# ESP32_with_USBC.net
KiCad netlist of a schematic drawn in Altium Designer
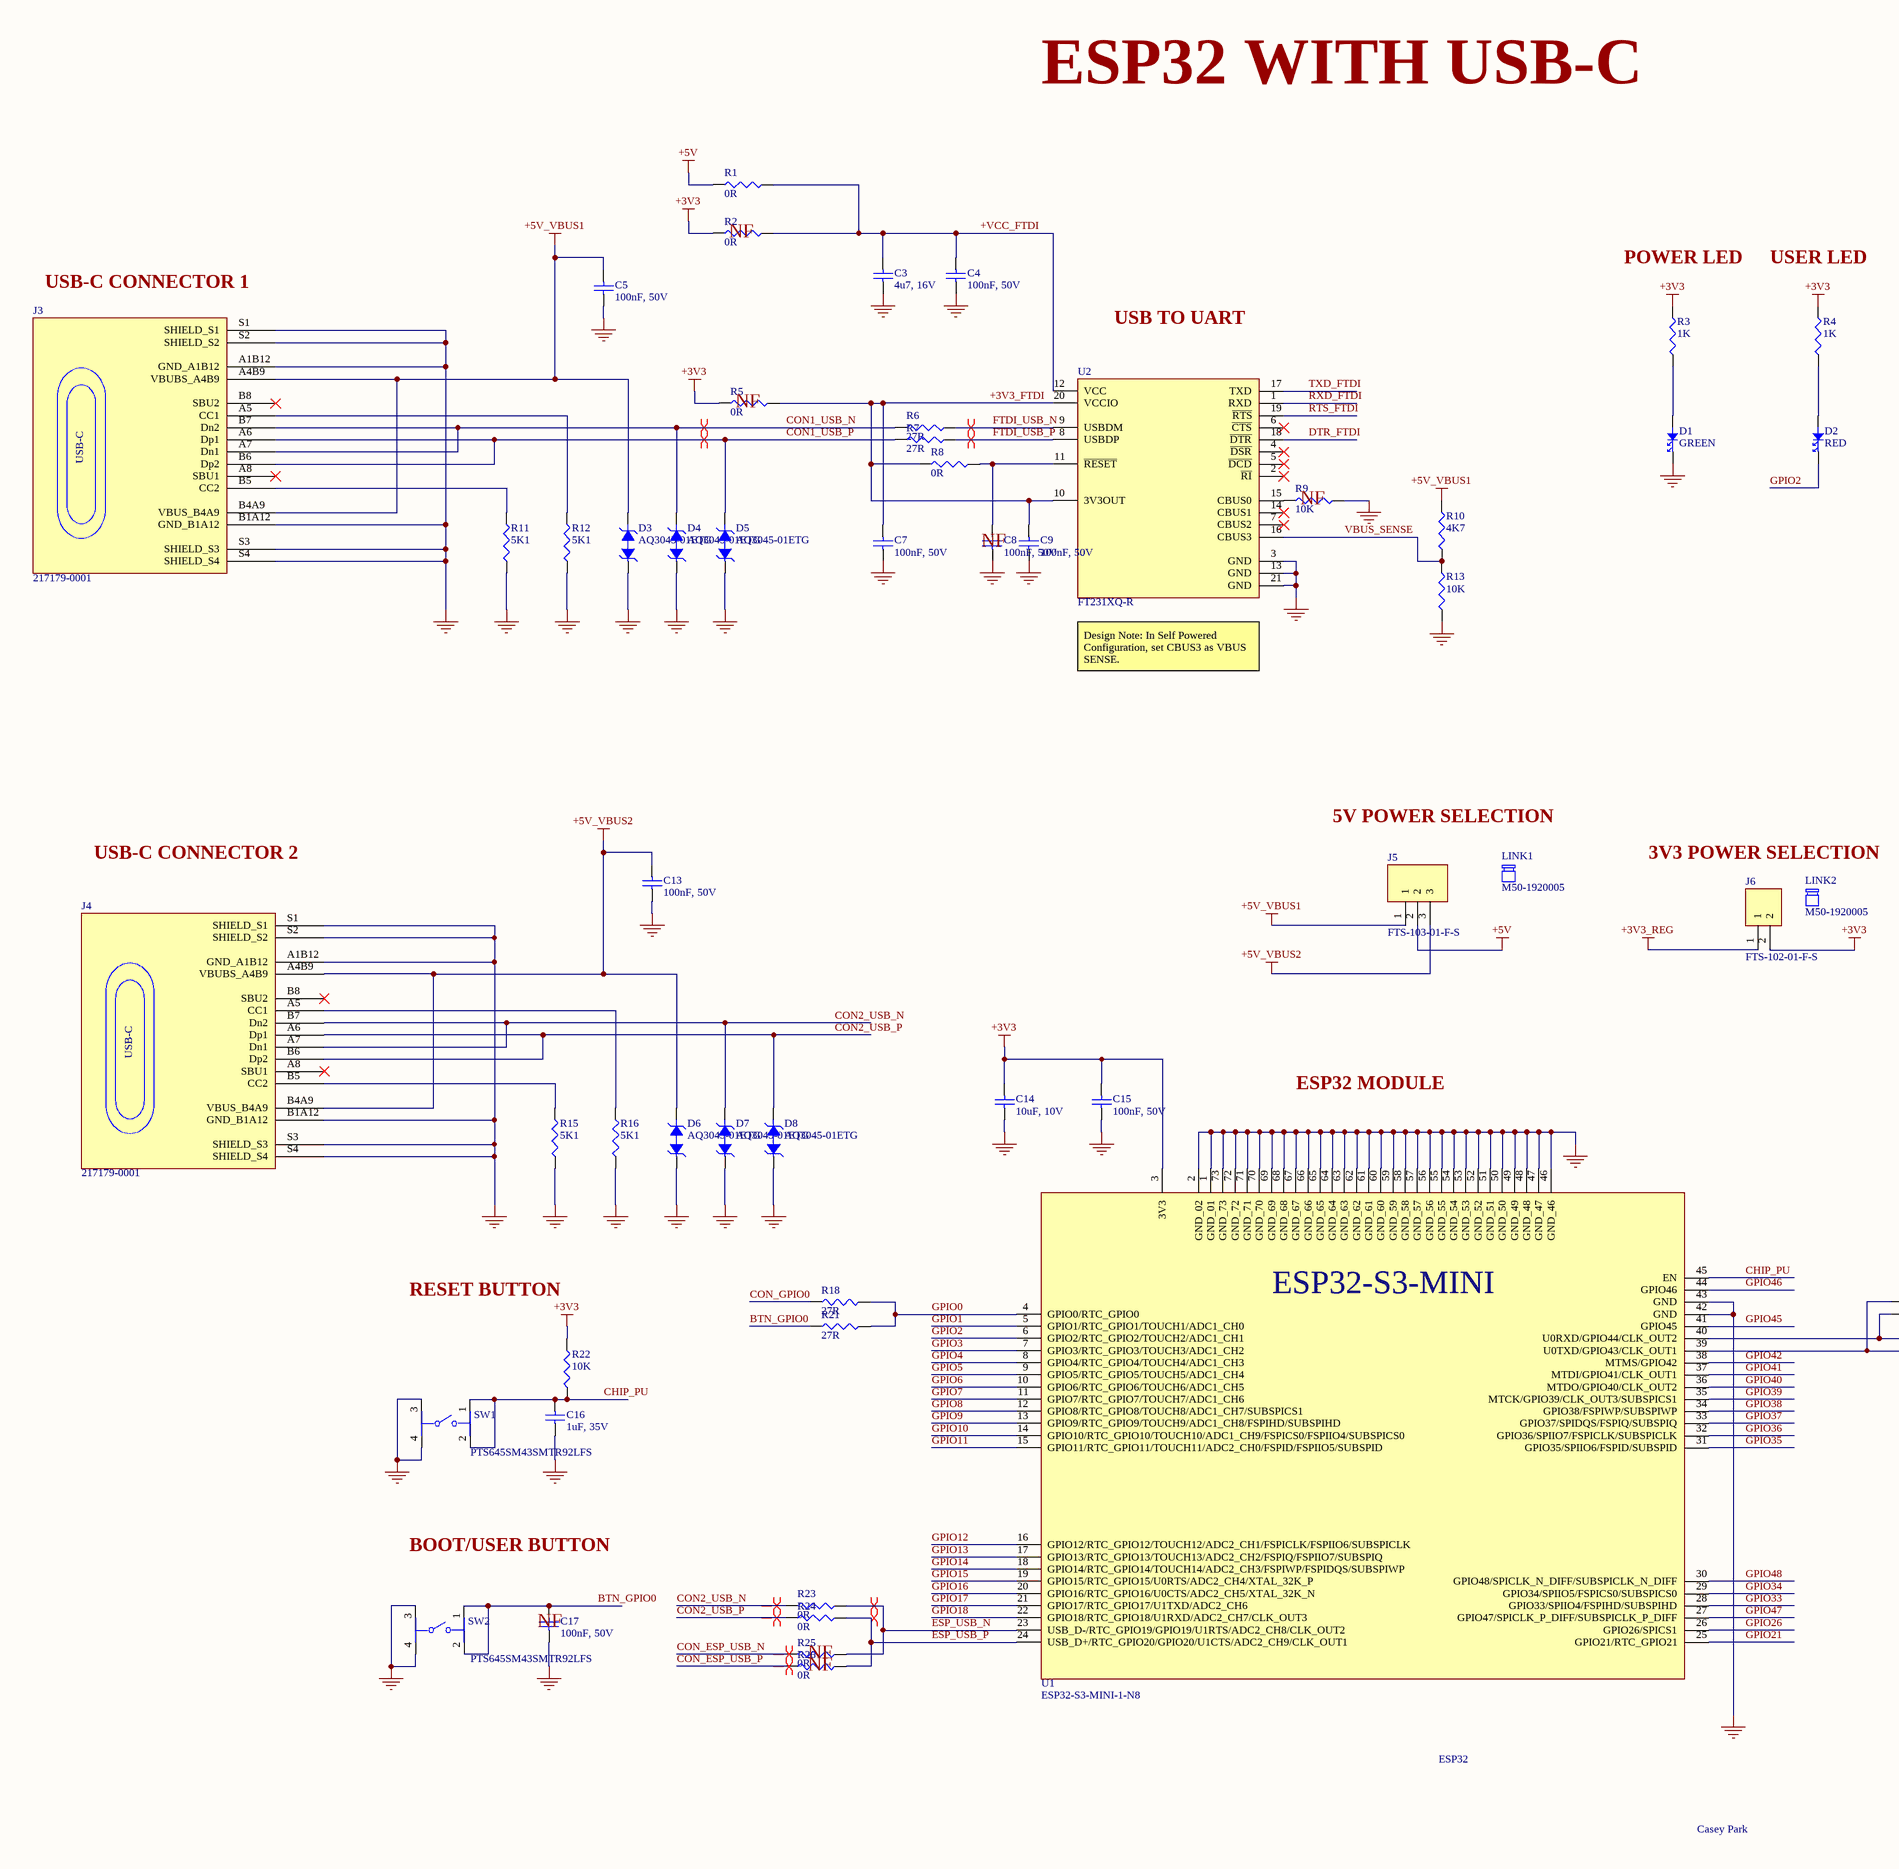
[diagram p0: ESP32 with USBC.SchDoc, left]
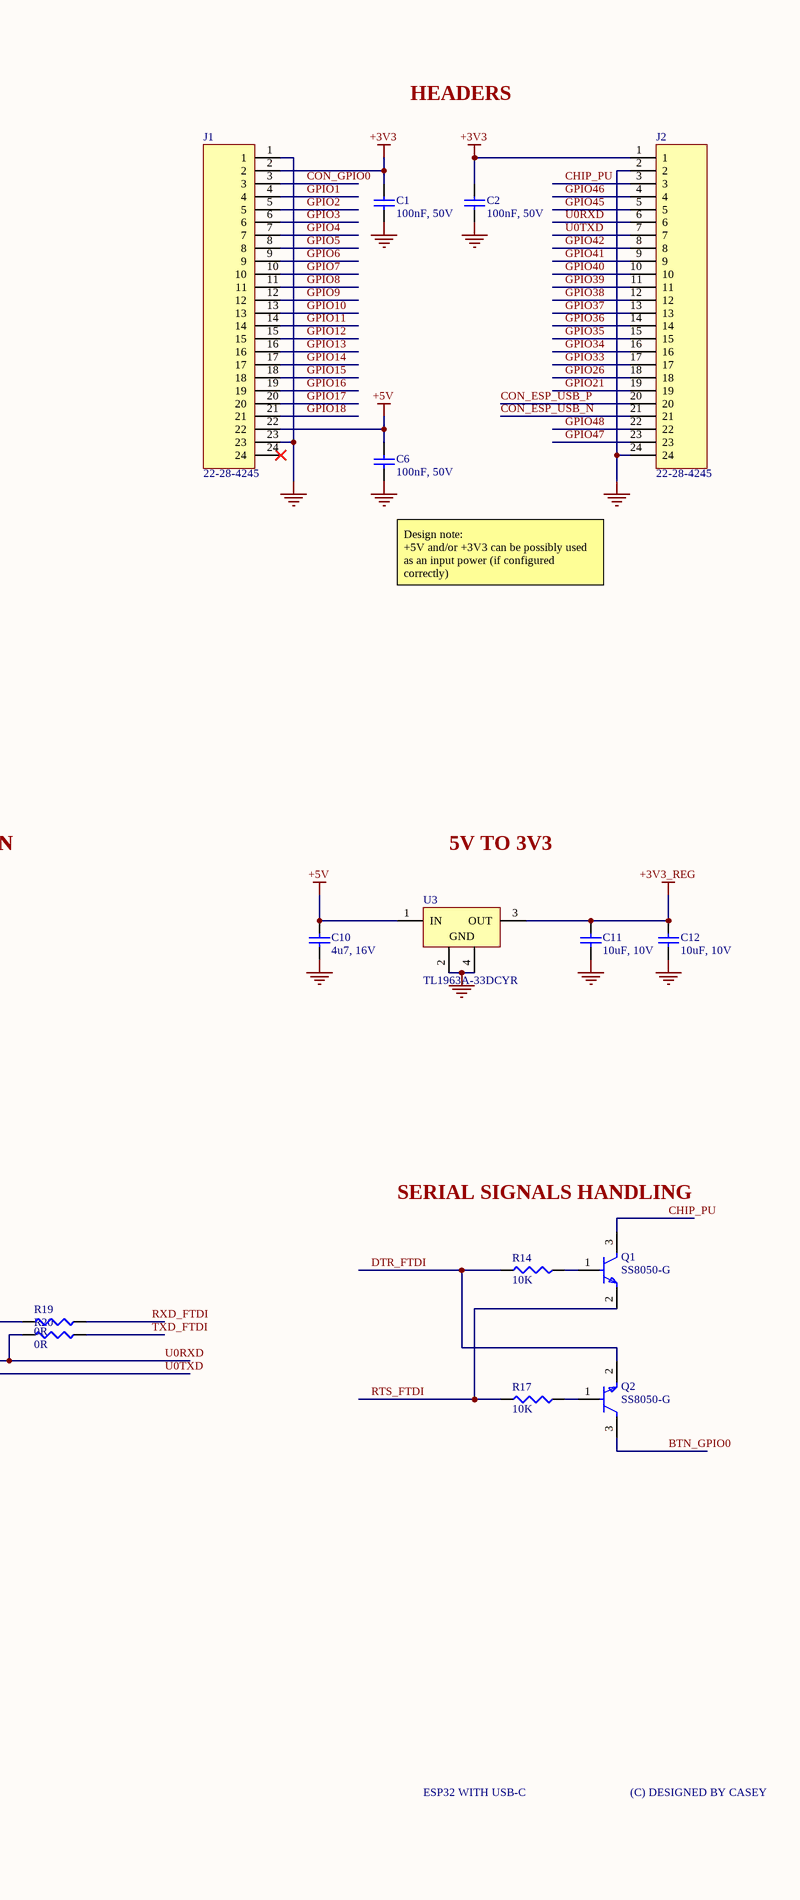
[diagram p1: ESP32 with USBC.SchDoc, right]

(export (version "E")
  (design (tool "Eeschema 10.0.6"))
  (components
    (comp (ref "C1")
      (value "100nF, 50V")
      (footprint "CAPC1005X70N")
      (description "CAP CER 0.1UF 50V X7R 0402")
      (fields
        (field (name "MANUFACTURER") "Samsung")
        (field (name "MANUFACTURER PART NUMBER") "CL05B104KB54PNC")
      )
      (libsource (lib "Schlib") (part "CL05B104KB54PNC"))
    )
    (comp (ref "C2")
      (value "100nF, 50V")
      (footprint "CAPC1005X70N")
      (description "CAP CER 0.1UF 50V X7R 0402")
      (fields
        (field (name "MANUFACTURER") "Samsung")
        (field (name "MANUFACTURER PART NUMBER") "CL05B104KB54PNC")
      )
      (libsource (lib "Schlib") (part "CL05B104KB54PNC"))
    )
    (comp (ref "C3")
      (value "4u7, 16V")
      (footprint "CAPC1005X70N")
      (description "CAP CER 4.7UF 16V X5R 0402")
      (fields
        (field (name "MANUFACTURER") "Samsung")
        (field (name "MANUFACTURER PART NUMBER") "CL05A475MO5NUNC")
      )
      (libsource (lib "Schlib") (part "CL05A475MO5NUNC"))
    )
    (comp (ref "C4")
      (value "100nF, 50V")
      (footprint "CAPC1005X70N")
      (description "CAP CER 0.1UF 50V X7R 0402")
      (fields
        (field (name "MANUFACTURER") "Samsung")
        (field (name "MANUFACTURER PART NUMBER") "CL05B104KB54PNC")
      )
      (libsource (lib "Schlib") (part "CL05B104KB54PNC"))
    )
    (comp (ref "C5")
      (value "100nF, 50V")
      (footprint "CAPC1005X70N")
      (description "CAP CER 0.1UF 50V X7R 0402")
      (fields
        (field (name "MANUFACTURER") "Samsung")
        (field (name "MANUFACTURER PART NUMBER") "CL05B104KB54PNC")
      )
      (libsource (lib "Schlib") (part "CL05B104KB54PNC"))
    )
    (comp (ref "C6")
      (value "100nF, 50V")
      (footprint "CAPC1005X70N")
      (description "CAP CER 0.1UF 50V X7R 0402")
      (fields
        (field (name "MANUFACTURER") "Samsung")
        (field (name "MANUFACTURER PART NUMBER") "CL05B104KB54PNC")
      )
      (libsource (lib "Schlib") (part "CL05B104KB54PNC"))
    )
    (comp (ref "C7")
      (value "100nF, 50V")
      (footprint "CAPC1005X70N")
      (description "CAP CER 0.1UF 50V X7R 0402")
      (fields
        (field (name "MANUFACTURER") "Samsung")
        (field (name "MANUFACTURER PART NUMBER") "CL05B104KB54PNC")
      )
      (libsource (lib "Schlib") (part "CL05B104KB54PNC"))
    )
    (comp (ref "C8")
      (value "100nF, 50V")
      (footprint "CAPC1005X70N")
      (description "CAP CER 0.1UF 50V X7R 0402")
      (fields
        (field (name "MANUFACTURER") "Samsung")
        (field (name "MANUFACTURER PART NUMBER") "CL05B104KB54PNC")
      )
      (libsource (lib "Schlib") (part "CL05B104KB54PNC"))
    )
    (comp (ref "C9")
      (value "100nF, 50V")
      (footprint "CAPC1005X70N")
      (description "CAP CER 0.1UF 50V X7R 0402")
      (fields
        (field (name "MANUFACTURER") "Samsung")
        (field (name "MANUFACTURER PART NUMBER") "CL05B104KB54PNC")
      )
      (libsource (lib "Schlib") (part "CL05B104KB54PNC"))
    )
    (comp (ref "C10")
      (value "4u7, 16V")
      (footprint "CAPC1005X70N")
      (description "CAP CER 4.7UF 16V X5R 0402")
      (fields
        (field (name "MANUFACTURER") "Samsung")
        (field (name "MANUFACTURER PART NUMBER") "CL05A475MO5NUNC")
      )
      (libsource (lib "Schlib") (part "CL05A475MO5NUNC"))
    )
    (comp (ref "C11")
      (value "10uF, 10V")
      (footprint "CAPC1005X70N")
      (description "10 µF ±20% 10V Ceramic Capacitor X5R 0402 (1005 Metric)")
      (fields
        (field (name "MANUFACTURER") "Samsung")
        (field (name "MANUFACTURER PART NUMBER") "CL05A106MP5NRNC")
      )
      (libsource (lib "Schlib") (part "CL05A106MP5NRNC"))
    )
    (comp (ref "C12")
      (value "10uF, 10V")
      (footprint "CAPC1005X70N")
      (description "10 µF ±20% 10V Ceramic Capacitor X5R 0402 (1005 Metric)")
      (fields
        (field (name "MANUFACTURER") "Samsung")
        (field (name "MANUFACTURER PART NUMBER") "CL05A106MP5NRNC")
      )
      (libsource (lib "Schlib") (part "CL05A106MP5NRNC"))
    )
    (comp (ref "C13")
      (value "100nF, 50V")
      (footprint "CAPC1005X70N")
      (description "CAP CER 0.1UF 50V X7R 0402")
      (fields
        (field (name "MANUFACTURER") "Samsung")
        (field (name "MANUFACTURER PART NUMBER") "CL05B104KB54PNC")
      )
      (libsource (lib "Schlib") (part "CL05B104KB54PNC"))
    )
    (comp (ref "C14")
      (value "10uF, 10V")
      (footprint "CAPC1005X70N")
      (description "10 µF ±20% 10V Ceramic Capacitor X5R 0402 (1005 Metric)")
      (fields
        (field (name "MANUFACTURER") "Samsung")
        (field (name "MANUFACTURER PART NUMBER") "CL05A106MP5NRNC")
      )
      (libsource (lib "Schlib") (part "CL05A106MP5NRNC"))
    )
    (comp (ref "C15")
      (value "100nF, 50V")
      (footprint "CAPC1005X70N")
      (description "CAP CER 0.1UF 50V X7R 0402")
      (fields
        (field (name "MANUFACTURER") "Samsung")
        (field (name "MANUFACTURER PART NUMBER") "CL05B104KB54PNC")
      )
      (libsource (lib "Schlib") (part "CL05B104KB54PNC"))
    )
    (comp (ref "C16")
      (value "1uF, 35V")
      (footprint "CAPC1005X70N")
      (description "CAP CER 1UF 35V X5R 0402")
      (fields
        (field (name "MANUFACTURER") "Samsung")
        (field (name "MANUFACTURER PART NUMBER") "CL05A105KL5NRNC")
      )
      (libsource (lib "Schlib") (part "CL05A105KL5NRNC"))
    )
    (comp (ref "C17")
      (value "100nF, 50V")
      (footprint "CAPC1005X70N")
      (description "CAP CER 0.1UF 50V X7R 0402")
      (fields
        (field (name "MANUFACTURER") "Samsung")
        (field (name "MANUFACTURER PART NUMBER") "CL05B104KB54PNC")
      )
      (libsource (lib "Schlib") (part "CL05B104KB54PNC"))
    )
    (comp (ref "D1")
      (value "GREEN")
      (footprint "LED0402GREEN")
      (description "LED YLW-GRN 0402 SMD")
      (fields
        (field (name "MANUFACTURER") "Vishay")
        (field (name "MANUFACTURER PART NUMBER") "VLMG1500-GS08")
      )
      (libsource (lib "Schlib") (part "VLMG1500-GS08"))
    )
    (comp (ref "D2")
      (value "RED")
      (footprint "LED0402RED")
      (description "LED RED 0402 SMD")
      (fields
        (field (name "MANUFACTURER") "Vishay")
        (field (name "MANUFACTURER PART NUMBER") "VLMS1500-GS08")
      )
      (libsource (lib "Schlib") (part "VLMS1500-GS08"))
    )
    (comp (ref "D3")
      (value "AQ3045-01ETG")
      (footprint "SOD882")
      (description "TVS DIODE 5.3VWM 12VC SOD882")
      (fields (field (name "MANUFACTURER") "Littelfuse") (field (name "LCSC PART NUMBER") "C3710326"))
      (libsource (lib "Schlib") (part "AQ3045-01ETG"))
    )
    (comp (ref "D4")
      (value "AQ3045-01ETG")
      (footprint "SOD882")
      (description "TVS DIODE 5.3VWM 12VC SOD882")
      (fields (field (name "MANUFACTURER") "Littelfuse") (field (name "LCSC PART NUMBER") "C3710326"))
      (libsource (lib "Schlib") (part "AQ3045-01ETG"))
    )
    (comp (ref "D5")
      (value "AQ3045-01ETG")
      (footprint "SOD882")
      (description "TVS DIODE 5.3VWM 12VC SOD882")
      (fields (field (name "MANUFACTURER") "Littelfuse") (field (name "LCSC PART NUMBER") "C3710326"))
      (libsource (lib "Schlib") (part "AQ3045-01ETG"))
    )
    (comp (ref "D6")
      (value "AQ3045-01ETG")
      (footprint "SOD882")
      (description "TVS DIODE 5.3VWM 12VC SOD882")
      (fields (field (name "MANUFACTURER") "Littelfuse") (field (name "LCSC PART NUMBER") "C3710326"))
      (libsource (lib "Schlib") (part "AQ3045-01ETG"))
    )
    (comp (ref "D7")
      (value "AQ3045-01ETG")
      (footprint "SOD882")
      (description "TVS DIODE 5.3VWM 12VC SOD882")
      (fields (field (name "MANUFACTURER") "Littelfuse") (field (name "LCSC PART NUMBER") "C3710326"))
      (libsource (lib "Schlib") (part "AQ3045-01ETG"))
    )
    (comp (ref "D8")
      (value "AQ3045-01ETG")
      (footprint "SOD882")
      (description "TVS DIODE 5.3VWM 12VC SOD882")
      (fields (field (name "MANUFACTURER") "Littelfuse") (field (name "LCSC PART NUMBER") "C3710326"))
      (libsource (lib "Schlib") (part "AQ3045-01ETG"))
    )
    (comp (ref "J1")
      (value "22-28-4245")
      (footprint "HDR_1X24_2.54MM")
      (description "CONN HEADER VERT 24POS 2.54MM")
      (fields (field (name "MANUFACTURER") "Molex") (field (name "LCSC PART NUMBER") "C7145888"))
      (libsource (lib "") (part "22-28-4245_1"))
    )
    (comp (ref "J2")
      (value "22-28-4245")
      (footprint "HDR_1X24_2.54MM")
      (description "CONN HEADER VERT 24POS 2.54MM")
      (fields (field (name "MANUFACTURER") "Molex") (field (name "LCSC PART NUMBER") "C7145888"))
      (libsource (lib "Schlib") (part "22-28-4245"))
    )
    (comp (ref "J3")
      (value "217179-0001")
      (footprint "FP-2171790001-MFG")
      (description "CONN RCP USB2.0 TYP C 24P SMD RA")
      (fields (field (name "MANUFACTURER") "Molex") (field (name "LCSC PART NUMBER") "C3197684"))
      (libsource (lib "Schlib") (part "217179-0001"))
    )
    (comp (ref "J4")
      (value "217179-0001")
      (footprint "FP-2171790001-MFG")
      (description "CONN RCP USB2.0 TYP C 24P SMD RA")
      (fields (field (name "MANUFACTURER") "Molex") (field (name "LCSC PART NUMBER") "C3197684"))
      (libsource (lib "Schlib") (part "217179-0001"))
    )
    (comp (ref "J5")
      (value "FTS-103-01-F-S")
      (footprint "HDR_1X3_1.27MM")
      (description "CONN HEADER VERT 3POS 1.27MM")
      (fields (field (name "MANUFACTURER") "Samtec") (field (name "LCSC PART NUMBER") "C3333578"))
      (libsource (lib "Schlib") (part "FTS-103-01-F-S"))
    )
    (comp (ref "J6")
      (value "FTS-102-01-F-S")
      (footprint "HDR_1X2_1.27MM")
      (description "CONN HEADER VERT 2POS 1.27MM")
      (fields (field (name "MANUFACTURER") "Samtec") (field (name "LCSC PART NUMBER") "C6045317"))
      (libsource (lib "Schlib") (part "FTS-102-01-F-S"))
    )
    (comp (ref "LINK1")
      (value "M50-1920005")
      (description "CONN SHUNT 1.27MM RED")
      (fields (field (name "MANUFACTURER") "Harwin") (field (name "LCSC PART NUMBER") "C6985646"))
      (libsource (lib "Schlib") (part "M50-1920005"))
    )
    (comp (ref "LINK2")
      (value "M50-1920005")
      (description "CONN SHUNT 1.27MM RED")
      (fields (field (name "MANUFACTURER") "Harwin") (field (name "LCSC PART NUMBER") "C6985646"))
      (libsource (lib "Schlib") (part "M50-1920005"))
    )
    (comp (ref "Q1")
      (value "SS8050-G")
      (footprint "FP-SS8050-G-IPC_B")
      (description "TRANS NPN 25V 1.5A SOT-23-3")
      (fields (field (name "MANUFACTURER") "Comchip") (field (name "LCSC PART NUMBER") "C164886"))
      (libsource (lib "Schlib") (part "SS8050-G"))
    )
    (comp (ref "Q2")
      (value "SS8050-G")
      (footprint "FP-SS8050-G-IPC_B")
      (description "TRANS NPN 25V 1.5A SOT-23-3")
      (fields (field (name "MANUFACTURER") "Comchip") (field (name "LCSC PART NUMBER") "C164886"))
      (libsource (lib "Schlib") (part "SS8050-G"))
    )
    (comp (ref "R1")
      (value "0R")
      (footprint "RESC1005X35N")
      (description "RES 0 OHM JUMPER 1/16W 0402")
      (fields
        (field (name "MANUFACTURER") "Yageo")
        (field (name "MANUFACTURER PART NUMBER") "RC0402FR-070RL")
      )
      (libsource (lib "Schlib") (part "RC0402FR-070RL"))
    )
    (comp (ref "R2")
      (value "0R")
      (footprint "RESC1005X35N")
      (description "RES 0 OHM JUMPER 1/16W 0402")
      (fields
        (field (name "MANUFACTURER") "Yageo")
        (field (name "MANUFACTURER PART NUMBER") "RC0402FR-070RL")
      )
      (libsource (lib "Schlib") (part "RC0402FR-070RL"))
    )
    (comp (ref "R3")
      (value "1K")
      (footprint "RESC1005X35N")
      (description "RES 1K OHM 1% 1/16W 0402")
      (fields
        (field (name "MANUFACTURER") "Yageo")
        (field (name "MANUFACTURER PART NUMBER") "RC0402FR-071KL")
      )
      (libsource (lib "Schlib") (part "RC0402FR-071KL"))
    )
    (comp (ref "R4")
      (value "1K")
      (footprint "RESC1005X35N")
      (description "RES 1K OHM 1% 1/16W 0402")
      (fields
        (field (name "MANUFACTURER") "Yageo")
        (field (name "MANUFACTURER PART NUMBER") "RC0402FR-071KL")
      )
      (libsource (lib "Schlib") (part "RC0402FR-071KL"))
    )
    (comp (ref "R5")
      (value "0R")
      (footprint "RESC1005X35N")
      (description "RES 0 OHM JUMPER 1/16W 0402")
      (fields
        (field (name "MANUFACTURER") "Yageo")
        (field (name "MANUFACTURER PART NUMBER") "RC0402FR-070RL")
      )
      (libsource (lib "Schlib") (part "RC0402FR-070RL"))
    )
    (comp (ref "R6")
      (value "27R")
      (footprint "RESC1005X35N")
      (description "RES 27 OHM 1% 1/16W 0402")
      (fields
        (field (name "MANUFACTURER") "Yageo")
        (field (name "MANUFACTURER PART NUMBER") "RC0402FR-0727RL")
      )
      (libsource (lib "Schlib") (part "RC0402FR-0727RL"))
    )
    (comp (ref "R7")
      (value "27R")
      (footprint "RESC1005X35N")
      (description "RES 27 OHM 1% 1/16W 0402")
      (fields
        (field (name "MANUFACTURER") "Yageo")
        (field (name "MANUFACTURER PART NUMBER") "RC0402FR-0727RL")
      )
      (libsource (lib "Schlib") (part "RC0402FR-0727RL"))
    )
    (comp (ref "R8")
      (value "0R")
      (footprint "RESC1005X35N")
      (description "RES 0 OHM JUMPER 1/16W 0402")
      (fields
        (field (name "MANUFACTURER") "Yageo")
        (field (name "MANUFACTURER PART NUMBER") "RC0402FR-070RL")
      )
      (libsource (lib "Schlib") (part "RC0402FR-070RL"))
    )
    (comp (ref "R9")
      (value "10K")
      (footprint "RESC1005X35N")
      (description "RES SMD 10K OHM 0.1% 1/16W 0402")
      (fields
        (field (name "MANUFACTURER") "Yageo")
        (field (name "MANUFACTURER PART NUMBER") "AT0402BRD0710KL")
      )
      (libsource (lib "Schlib") (part "AT0402BRD0710KL"))
    )
    (comp (ref "R10")
      (value "4K7")
      (footprint "RESC1005X35N")
      (description "RES 4.7K OHM 1% 1/16W 0402")
      (fields
        (field (name "MANUFACTURER") "Yageo")
        (field (name "MANUFACTURER PART NUMBER") "RC0402FR-074K7L")
      )
      (libsource (lib "Schlib") (part "RC0402FR-074K7L"))
    )
    (comp (ref "R11")
      (value "5K1")
      (footprint "RESC1005X35N")
      (description "RES SMD 5.1K OHM 1% 1/16W 0402")
      (fields
        (field (name "MANUFACTURER") "Yageo")
        (field (name "MANUFACTURER PART NUMBER") "AC0402FR-075K1L")
      )
      (libsource (lib "Schlib") (part "AC0402FR-075K1L"))
    )
    (comp (ref "R12")
      (value "5K1")
      (footprint "RESC1005X35N")
      (description "RES SMD 5.1K OHM 1% 1/16W 0402")
      (fields
        (field (name "MANUFACTURER") "Yageo")
        (field (name "MANUFACTURER PART NUMBER") "AC0402FR-075K1L")
      )
      (libsource (lib "Schlib") (part "AC0402FR-075K1L"))
    )
    (comp (ref "R13")
      (value "10K")
      (footprint "RESC1005X35N")
      (description "RES SMD 10K OHM 0.1% 1/16W 0402")
      (fields
        (field (name "MANUFACTURER") "Yageo")
        (field (name "MANUFACTURER PART NUMBER") "AT0402BRD0710KL")
      )
      (libsource (lib "Schlib") (part "AT0402BRD0710KL"))
    )
    (comp (ref "R14")
      (value "10K")
      (footprint "RESC1005X35N")
      (description "RES SMD 10K OHM 0.1% 1/16W 0402")
      (fields
        (field (name "MANUFACTURER") "Yageo")
        (field (name "MANUFACTURER PART NUMBER") "AT0402BRD0710KL")
      )
      (libsource (lib "Schlib") (part "AT0402BRD0710KL"))
    )
    (comp (ref "R15")
      (value "5K1")
      (footprint "RESC1005X35N")
      (description "RES SMD 5.1K OHM 1% 1/16W 0402")
      (fields
        (field (name "MANUFACTURER") "Yageo")
        (field (name "MANUFACTURER PART NUMBER") "AC0402FR-075K1L")
      )
      (libsource (lib "Schlib") (part "AC0402FR-075K1L"))
    )
    (comp (ref "R16")
      (value "5K1")
      (footprint "RESC1005X35N")
      (description "RES SMD 5.1K OHM 1% 1/16W 0402")
      (fields
        (field (name "MANUFACTURER") "Yageo")
        (field (name "MANUFACTURER PART NUMBER") "AC0402FR-075K1L")
      )
      (libsource (lib "Schlib") (part "AC0402FR-075K1L"))
    )
    (comp (ref "R17")
      (value "10K")
      (footprint "RESC1005X35N")
      (description "RES SMD 10K OHM 0.1% 1/16W 0402")
      (fields
        (field (name "MANUFACTURER") "Yageo")
        (field (name "MANUFACTURER PART NUMBER") "AT0402BRD0710KL")
      )
      (libsource (lib "Schlib") (part "AT0402BRD0710KL"))
    )
    (comp (ref "R18")
      (value "27R")
      (footprint "RESC1005X35N")
      (description "RES 27 OHM 1% 1/16W 0402")
      (fields
        (field (name "MANUFACTURER") "Yageo")
        (field (name "MANUFACTURER PART NUMBER") "RC0402FR-0727RL")
      )
      (libsource (lib "Schlib") (part "RC0402FR-0727RL"))
    )
    (comp (ref "R19")
      (value "0R")
      (footprint "RESC1005X35N")
      (description "RES 0 OHM JUMPER 1/16W 0402")
      (fields
        (field (name "MANUFACTURER") "Yageo")
        (field (name "MANUFACTURER PART NUMBER") "RC0402FR-070RL")
      )
      (libsource (lib "Schlib") (part "RC0402FR-070RL"))
    )
    (comp (ref "R20")
      (value "0R")
      (footprint "RESC1005X35N")
      (description "RES 0 OHM JUMPER 1/16W 0402")
      (fields
        (field (name "MANUFACTURER") "Yageo")
        (field (name "MANUFACTURER PART NUMBER") "RC0402FR-070RL")
      )
      (libsource (lib "Schlib") (part "RC0402FR-070RL"))
    )
    (comp (ref "R21")
      (value "27R")
      (footprint "RESC1005X35N")
      (description "RES 27 OHM 1% 1/16W 0402")
      (fields
        (field (name "MANUFACTURER") "Yageo")
        (field (name "MANUFACTURER PART NUMBER") "RC0402FR-0727RL")
      )
      (libsource (lib "Schlib") (part "RC0402FR-0727RL"))
    )
    (comp (ref "R22")
      (value "10K")
      (footprint "RESC1005X35N")
      (description "RES SMD 10K OHM 0.1% 1/16W 0402")
      (fields
        (field (name "MANUFACTURER") "Yageo")
        (field (name "MANUFACTURER PART NUMBER") "AT0402BRD0710KL")
      )
      (libsource (lib "Schlib") (part "AT0402BRD0710KL"))
    )
    (comp (ref "R23")
      (value "0R")
      (footprint "RESC1005X35N")
      (description "RES 0 OHM JUMPER 1/16W 0402")
      (fields
        (field (name "MANUFACTURER") "Yageo")
        (field (name "MANUFACTURER PART NUMBER") "RC0402FR-070RL")
      )
      (libsource (lib "Schlib") (part "RC0402FR-070RL"))
    )
    (comp (ref "R24")
      (value "0R")
      (footprint "RESC1005X35N")
      (description "RES 0 OHM JUMPER 1/16W 0402")
      (fields
        (field (name "MANUFACTURER") "Yageo")
        (field (name "MANUFACTURER PART NUMBER") "RC0402FR-070RL")
      )
      (libsource (lib "Schlib") (part "RC0402FR-070RL"))
    )
    (comp (ref "R25")
      (value "0R")
      (footprint "RESC1005X35N")
      (description "RES 0 OHM JUMPER 1/16W 0402")
      (fields
        (field (name "MANUFACTURER") "Yageo")
        (field (name "MANUFACTURER PART NUMBER") "RC0402FR-070RL")
      )
      (libsource (lib "Schlib") (part "RC0402FR-070RL"))
    )
    (comp (ref "R26")
      (value "0R")
      (footprint "RESC1005X35N")
      (description "RES 0 OHM JUMPER 1/16W 0402")
      (fields
        (field (name "MANUFACTURER") "Yageo")
        (field (name "MANUFACTURER PART NUMBER") "RC0402FR-070RL")
      )
      (libsource (lib "Schlib") (part "RC0402FR-070RL"))
    )
    (comp (ref "SW1")
      (value "PTS645SM43SMTR92LFS")
      (footprint "FP-PTS645SM43SMTR92LFS-MFG")
      (description "SWITCH TACTILE SPST-NO 0.05A 12V")
      (fields (field (name "MANUFACTURER") "ITT C&K") (field (name "LCSC PART NUMBER") "C221880"))
      (libsource (lib "Schlib") (part "PTS645SM43SMTR92LFS"))
    )
    (comp (ref "SW2")
      (value "PTS645SM43SMTR92LFS")
      (footprint "FP-PTS645SM43SMTR92LFS-MFG")
      (description "SWITCH TACTILE SPST-NO 0.05A 12V")
      (fields (field (name "MANUFACTURER") "ITT C&K") (field (name "LCSC PART NUMBER") "C221880"))
      (libsource (lib "Schlib") (part "PTS645SM43SMTR92LFS"))
    )
    (comp (ref "U1")
      (value "ESP32-S3-MINI-1-N8")
      (footprint "XCVR_ESP32-S3-MINI-1-N8")
      (description "SMD module, ESP32-S3FN8, 8 MB SPI flash, PCB antenna")
      (fields (field (name "MANUFACTURER") "Espressif Systems") (field (name "LCSC PART NUMBER") "C2913206"))
      (libsource (lib "Schlib") (part "ESP32-S3-MINI-1-N8"))
    )
    (comp (ref "U2")
      (value "FT231XQ-R")
      (footprint "FP-QFN-20-IPC_B")
      (description "IC USB SERIAL FULL UART 20QFN")
      (fields (field (name "MANUFACTURER") "FTDI") (field (name "LCSC PART NUMBER") "C132159"))
      (libsource (lib "Schlib") (part "FT231XQ-R"))
    )
    (comp (ref "U3")
      (value "TL1963A-33DCYR")
      (footprint "DCY0004A_N")
      (description "IC REG LIN 3.3V 1.5A SOT-223-4")
      (fields (field (name "MANUFACTURER") "Texas Instruments") (field (name "LCSC PART NUMBER") "C181262"))
      (libsource (lib "Schlib") (part "TL1963A-33DCYR"))
    )
  )
  (nets
    (net (code "1") (name "+3V3") (class "Default")
      (node (ref "C1") (pin "2") (pinfunction "2_2") (pintype "passive"))
      (node (ref "C14") (pin "2") (pinfunction "2_2") (pintype "passive"))
      (node (ref "C15") (pin "2") (pinfunction "2_2") (pintype "passive"))
      (node (ref "C2") (pin "2") (pinfunction "2_2") (pintype "passive"))
      (node (ref "J1") (pin "2") (pinfunction "2_2") (pintype "passive"))
      (node (ref "J2") (pin "1") (pinfunction "1_1") (pintype "passive"))
      (node (ref "J6") (pin "2") (pinfunction "2_2") (pintype "passive"))
      (node (ref "R2") (pin "1") (pinfunction "1_1") (pintype "passive"))
      (node (ref "R22") (pin "2") (pinfunction "2_2") (pintype "passive"))
      (node (ref "R3") (pin "2") (pinfunction "2_2") (pintype "passive"))
      (node (ref "R4") (pin "2") (pinfunction "2_2") (pintype "passive"))
      (node (ref "R5") (pin "1") (pinfunction "1_1") (pintype "passive"))
      (node (ref "U1") (pin "3") (pinfunction "3V3_3") (pintype "passive"))
    )
    (net (code "2") (name "+3V3_REG") (class "Default")
      (node (ref "C11") (pin "2") (pinfunction "2_2") (pintype "passive"))
      (node (ref "C12") (pin "2") (pinfunction "2_2") (pintype "passive"))
      (node (ref "J6") (pin "1") (pinfunction "1_1") (pintype "passive"))
      (node (ref "U3") (pin "3") (pinfunction "OUT_3") (pintype "power_in"))
    )
    (net (code "3") (name "+5V") (class "Default")
      (node (ref "C10") (pin "2") (pinfunction "2_2") (pintype "passive"))
      (node (ref "C6") (pin "2") (pinfunction "2_2") (pintype "passive"))
      (node (ref "J1") (pin "22") (pinfunction "22_22") (pintype "passive"))
      (node (ref "J5") (pin "2") (pinfunction "2_2") (pintype "passive"))
      (node (ref "R1") (pin "1") (pinfunction "1_1") (pintype "passive"))
      (node (ref "U3") (pin "1") (pinfunction "IN_1") (pintype "power_in"))
    )
    (net (code "4") (name "+5V_VBUS1") (class "Default")
      (node (ref "C5") (pin "2") (pinfunction "2_2") (pintype "passive"))
      (node (ref "D3") (pin "2") (pinfunction "2_2") (pintype "passive"))
      (node (ref "J3") (pin "A4B9") (pinfunction "VBUBS_A4B9_A4B9") (pintype "passive"))
      (node (ref "J3") (pin "B4A9") (pinfunction "VBUS_B4A9_B4A9") (pintype "passive"))
      (node (ref "J5") (pin "1") (pinfunction "1_1") (pintype "passive"))
      (node (ref "R10") (pin "2") (pinfunction "2_2") (pintype "passive"))
    )
    (net (code "5") (name "+5V_VBUS2") (class "Default")
      (node (ref "C13") (pin "2") (pinfunction "2_2") (pintype "passive"))
      (node (ref "D6") (pin "2") (pinfunction "2_2") (pintype "passive"))
      (node (ref "J4") (pin "A4B9") (pinfunction "VBUBS_A4B9_A4B9") (pintype "passive"))
      (node (ref "J4") (pin "B4A9") (pinfunction "VBUS_B4A9_B4A9") (pintype "passive"))
      (node (ref "J5") (pin "3") (pinfunction "3_3") (pintype "passive"))
    )
    (net (code "6") (name "/+3V3_FTDI") (class "Default")
      (node (ref "C7") (pin "2") (pinfunction "2_2") (pintype "passive"))
      (node (ref "C9") (pin "2") (pinfunction "2_2") (pintype "passive"))
      (node (ref "R5") (pin "2") (pinfunction "2_2") (pintype "passive"))
      (node (ref "R8") (pin "1") (pinfunction "1_1") (pintype "passive"))
      (node (ref "U2") (pin "10") (pinfunction "3V3OUT_10") (pintype "passive"))
      (node (ref "U2") (pin "20") (pinfunction "VCCIO_20") (pintype "passive"))
    )
    (net (code "7") (name "/+VCC_FTDI") (class "Default")
      (node (ref "C3") (pin "2") (pinfunction "2_2") (pintype "passive"))
      (node (ref "C4") (pin "2") (pinfunction "2_2") (pintype "passive"))
      (node (ref "R1") (pin "2") (pinfunction "2_2") (pintype "passive"))
      (node (ref "R2") (pin "2") (pinfunction "2_2") (pintype "passive"))
      (node (ref "U2") (pin "12") (pinfunction "VCC_12") (pintype "passive"))
    )
    (net (code "8") (name "/BTN_GPIO0") (class "Default")
      (node (ref "C17") (pin "2") (pinfunction "2_2") (pintype "passive"))
      (node (ref "Q2") (pin "3") (pinfunction "C_3") (pintype "passive"))
      (node (ref "R21") (pin "1") (pinfunction "1_1") (pintype "passive"))
      (node (ref "SW2") (pin "1") (pinfunction "1_1") (pintype "passive"))
      (node (ref "SW2") (pin "2") (pinfunction "2_2") (pintype "passive"))
    )
    (net (code "9") (name "/CHIP_PU") (class "Default")
      (node (ref "C16") (pin "2") (pinfunction "2_2") (pintype "passive"))
      (node (ref "J2") (pin "3") (pinfunction "3_3") (pintype "passive"))
      (node (ref "Q1") (pin "3") (pinfunction "C_3") (pintype "passive"))
      (node (ref "R22") (pin "1") (pinfunction "1_1") (pintype "passive"))
      (node (ref "SW1") (pin "1") (pinfunction "1_1") (pintype "passive"))
      (node (ref "SW1") (pin "2") (pinfunction "2_2") (pintype "passive"))
      (node (ref "U1") (pin "45") (pinfunction "EN_45") (pintype "passive"))
    )
    (net (code "10") (name "/CON1_USB_N") (class "Default")
      (node (ref "D4") (pin "2") (pinfunction "2_2") (pintype "passive"))
      (node (ref "J3") (pin "A7") (pinfunction "Dn1_A7") (pintype "passive"))
      (node (ref "J3") (pin "B7") (pinfunction "Dn2_B7") (pintype "passive"))
      (node (ref "R6") (pin "1") (pinfunction "1_1") (pintype "passive"))
    )
    (net (code "11") (name "/CON1_USB_P") (class "Default")
      (node (ref "D5") (pin "2") (pinfunction "2_2") (pintype "passive"))
      (node (ref "J3") (pin "A6") (pinfunction "Dp1_A6") (pintype "passive"))
      (node (ref "J3") (pin "B6") (pinfunction "Dp2_B6") (pintype "passive"))
      (node (ref "R7") (pin "1") (pinfunction "1_1") (pintype "passive"))
    )
    (net (code "12") (name "/CON2_USB_N") (class "Default")
      (node (ref "D7") (pin "2") (pinfunction "2_2") (pintype "passive"))
      (node (ref "J4") (pin "A7") (pinfunction "Dn1_A7") (pintype "passive"))
      (node (ref "J4") (pin "B7") (pinfunction "Dn2_B7") (pintype "passive"))
      (node (ref "R23") (pin "1") (pinfunction "1_1") (pintype "passive"))
    )
    (net (code "13") (name "/CON2_USB_P") (class "Default")
      (node (ref "D8") (pin "2") (pinfunction "2_2") (pintype "passive"))
      (node (ref "J4") (pin "A6") (pinfunction "Dp1_A6") (pintype "passive"))
      (node (ref "J4") (pin "B6") (pinfunction "Dp2_B6") (pintype "passive"))
      (node (ref "R24") (pin "1") (pinfunction "1_1") (pintype "passive"))
    )
    (net (code "14") (name "/CON_ESP_USB_N") (class "Default")
      (node (ref "J2") (pin "21") (pinfunction "21_21") (pintype "passive"))
      (node (ref "R25") (pin "1") (pinfunction "1_1") (pintype "passive"))
    )
    (net (code "15") (name "/CON_ESP_USB_P") (class "Default")
      (node (ref "J2") (pin "20") (pinfunction "20_20") (pintype "passive"))
      (node (ref "R26") (pin "1") (pinfunction "1_1") (pintype "passive"))
    )
    (net (code "16") (name "/CON_GPIO0") (class "Default")
      (node (ref "J1") (pin "3") (pinfunction "3_3") (pintype "passive"))
      (node (ref "R18") (pin "1") (pinfunction "1_1") (pintype "passive"))
    )
    (net (code "17") (name "/DTR_FTDI") (class "Default")
      (node (ref "Q2") (pin "2") (pinfunction "E_2") (pintype "passive"))
      (node (ref "R14") (pin "2") (pinfunction "2_2") (pintype "passive"))
      (node (ref "U2") (pin "18") (pinfunction "~{DTR}_18") (pintype "passive"))
    )
    (net (code "18") (name "/ESP_USB_N") (class "Default")
      (node (ref "R23") (pin "2") (pinfunction "2_2") (pintype "passive"))
      (node (ref "R25") (pin "2") (pinfunction "2_2") (pintype "passive"))
      (node (ref "U1") (pin "23") (pinfunction "USB_D-/RTC_GPIO19/GPIO19/U1RTS/ADC2_CH8/CLK_OUT2_23") (pintype "passive"))
    )
    (net (code "19") (name "/ESP_USB_P") (class "Default")
      (node (ref "R24") (pin "2") (pinfunction "2_2") (pintype "passive"))
      (node (ref "R26") (pin "2") (pinfunction "2_2") (pintype "passive"))
      (node (ref "U1") (pin "24") (pinfunction "USB_D+/RTC_GPIO20/GPIO20/U1CTS/ADC2_CH9/CLK_OUT1_24") (pintype "passive"))
    )
    (net (code "20") (name "/FTDI_USB_N") (class "Default")
      (node (ref "R6") (pin "2") (pinfunction "2_2") (pintype "passive"))
      (node (ref "U2") (pin "9") (pinfunction "USBDM_9") (pintype "passive"))
    )
    (net (code "21") (name "/FTDI_USB_P") (class "Default")
      (node (ref "R7") (pin "2") (pinfunction "2_2") (pintype "passive"))
      (node (ref "U2") (pin "8") (pinfunction "USBDP_8") (pintype "passive"))
    )
    (net (code "22") (name "/GPIO0") (class "Default")
      (node (ref "R18") (pin "2") (pinfunction "2_2") (pintype "passive"))
      (node (ref "R21") (pin "2") (pinfunction "2_2") (pintype "passive"))
      (node (ref "U1") (pin "4") (pinfunction "GPIO0/RTC_GPIO0_4") (pintype "passive"))
    )
    (net (code "23") (name "/GPIO1") (class "Default")
      (node (ref "J1") (pin "4") (pinfunction "4_4") (pintype "passive"))
      (node (ref "U1") (pin "5") (pinfunction "GPIO1/RTC_GPIO1/TOUCH1/ADC1_CH0_5") (pintype "passive"))
    )
    (net (code "24") (name "/GPIO2") (class "Default")
      (node (ref "D2") (pin "1") (pinfunction "1_1") (pintype "passive"))
      (node (ref "J1") (pin "5") (pinfunction "5_5") (pintype "passive"))
      (node (ref "U1") (pin "6") (pinfunction "GPIO2/RTC_GPIO2/TOUCH2/ADC1_CH1_6") (pintype "passive"))
    )
    (net (code "25") (name "/GPIO3") (class "Default")
      (node (ref "J1") (pin "6") (pinfunction "6_6") (pintype "passive"))
      (node (ref "U1") (pin "7") (pinfunction "GPIO3/RTC_GPIO3/TOUCH3/ADC1_CH2_7") (pintype "passive"))
    )
    (net (code "26") (name "/GPIO4") (class "Default")
      (node (ref "J1") (pin "7") (pinfunction "7_7") (pintype "passive"))
      (node (ref "U1") (pin "8") (pinfunction "GPIO4/RTC_GPIO4/TOUCH4/ADC1_CH3_8") (pintype "passive"))
    )
    (net (code "27") (name "/GPIO5") (class "Default")
      (node (ref "J1") (pin "8") (pinfunction "8_8") (pintype "passive"))
      (node (ref "U1") (pin "9") (pinfunction "GPIO5/RTC_GPIO5/TOUCH5/ADC1_CH4_9") (pintype "passive"))
    )
    (net (code "28") (name "/GPIO6") (class "Default")
      (node (ref "J1") (pin "9") (pinfunction "9_9") (pintype "passive"))
      (node (ref "U1") (pin "10") (pinfunction "GPIO6/RTC_GPIO6/TOUCH6/ADC1_CH5_10") (pintype "passive"))
    )
    (net (code "29") (name "/GPIO7") (class "Default")
      (node (ref "J1") (pin "10") (pinfunction "10_10") (pintype "passive"))
      (node (ref "U1") (pin "11") (pinfunction "GPIO7/RTC_GPIO7/TOUCH7/ADC1_CH6_11") (pintype "passive"))
    )
    (net (code "30") (name "/GPIO8") (class "Default")
      (node (ref "J1") (pin "11") (pinfunction "11_11") (pintype "passive"))
      (node (ref "U1") (pin "12") (pinfunction "GPIO8/RTC_GPIO8/TOUCH8/ADC1_CH7/SUBSPICS1_12") (pintype "passive"))
    )
    (net (code "31") (name "/GPIO9") (class "Default")
      (node (ref "J1") (pin "12") (pinfunction "12_12") (pintype "passive"))
      (node (ref "U1") (pin "13") (pinfunction "GPIO9/RTC_GPIO9/TOUCH9/ADC1_CH8/FSPIHD/SUBSPIHD_13") (pintype "passive"))
    )
    (net (code "32") (name "/GPIO10") (class "Default")
      (node (ref "J1") (pin "13") (pinfunction "13_13") (pintype "passive"))
      (node (ref "U1") (pin "14") (pinfunction "GPIO10/RTC_GPIO10/TOUCH10/ADC1_CH9/FSPICS0/FSPIIO4/SUBSPICS0_14") (pintype "passive"))
    )
    (net (code "33") (name "/GPIO11") (class "Default")
      (node (ref "J1") (pin "14") (pinfunction "14_14") (pintype "passive"))
      (node (ref "U1") (pin "15") (pinfunction "GPIO11/RTC_GPIO11/TOUCH11/ADC2_CH0/FSPID/FSPIIO5/SUBSPID_15") (pintype "passive"))
    )
    (net (code "34") (name "/GPIO12") (class "Default")
      (node (ref "J1") (pin "15") (pinfunction "15_15") (pintype "passive"))
      (node (ref "U1") (pin "16") (pinfunction "GPIO12/RTC_GPIO12/TOUCH12/ADC2_CH1/FSPICLK/FSPIIO6/SUBSPICLK_16") (pintype "passive"))
    )
    (net (code "35") (name "/GPIO13") (class "Default")
      (node (ref "J1") (pin "16") (pinfunction "16_16") (pintype "passive"))
      (node (ref "U1") (pin "17") (pinfunction "GPIO13/RTC_GPIO13/TOUCH13/ADC2_CH2/FSPIQ/FSPIIO7/SUBSPIQ_17") (pintype "passive"))
    )
    (net (code "36") (name "/GPIO14") (class "Default")
      (node (ref "J1") (pin "17") (pinfunction "17_17") (pintype "passive"))
      (node (ref "U1") (pin "18") (pinfunction "GPIO14/RTC_GPIO14/TOUCH14/ADC2_CH3/FSPIWP/FSPIDQS/SUBSPIWP_18") (pintype "passive"))
    )
    (net (code "37") (name "/GPIO15") (class "Default")
      (node (ref "J1") (pin "18") (pinfunction "18_18") (pintype "passive"))
      (node (ref "U1") (pin "19") (pinfunction "GPIO15/RTC_GPIO15/U0RTS/ADC2_CH4/XTAL_32K_P_19") (pintype "passive"))
    )
    (net (code "38") (name "/GPIO16") (class "Default")
      (node (ref "J1") (pin "19") (pinfunction "19_19") (pintype "passive"))
      (node (ref "U1") (pin "20") (pinfunction "GPIO16/RTC_GPIO16/U0CTS/ADC2_CH5/XTAL_32K_N_20") (pintype "passive"))
    )
    (net (code "39") (name "/GPIO17") (class "Default")
      (node (ref "J1") (pin "20") (pinfunction "20_20") (pintype "passive"))
      (node (ref "U1") (pin "21") (pinfunction "GPIO17/RTC_GPIO17/U1TXD/ADC2_CH6_21") (pintype "passive"))
    )
    (net (code "40") (name "/GPIO18") (class "Default")
      (node (ref "J1") (pin "21") (pinfunction "21_21") (pintype "passive"))
      (node (ref "U1") (pin "22") (pinfunction "GPIO18/RTC_GPIO18/U1RXD/ADC2_CH7/CLK_OUT3_22") (pintype "passive"))
    )
    (net (code "41") (name "/GPIO21") (class "Default")
      (node (ref "J2") (pin "19") (pinfunction "19_19") (pintype "passive"))
      (node (ref "U1") (pin "25") (pinfunction "GPIO21/RTC_GPIO21_25") (pintype "passive"))
    )
    (net (code "42") (name "/GPIO26") (class "Default")
      (node (ref "J2") (pin "18") (pinfunction "18_18") (pintype "passive"))
      (node (ref "U1") (pin "26") (pinfunction "GPIO26/SPICS1_26") (pintype "passive"))
    )
    (net (code "43") (name "/GPIO33") (class "Default")
      (node (ref "J2") (pin "17") (pinfunction "17_17") (pintype "passive"))
      (node (ref "U1") (pin "28") (pinfunction "GPIO33/SPIIO4/FSPIHD/SUBSPIHD_28") (pintype "passive"))
    )
    (net (code "44") (name "/GPIO34") (class "Default")
      (node (ref "J2") (pin "16") (pinfunction "16_16") (pintype "passive"))
      (node (ref "U1") (pin "29") (pinfunction "GPIO34/SPIIO5/FSPICS0/SUBSPICS0_29") (pintype "passive"))
    )
    (net (code "45") (name "/GPIO35") (class "Default")
      (node (ref "J2") (pin "15") (pinfunction "15_15") (pintype "passive"))
      (node (ref "U1") (pin "31") (pinfunction "GPIO35/SPIIO6/FSPID/SUBSPID_31") (pintype "passive"))
    )
    (net (code "46") (name "/GPIO36") (class "Default")
      (node (ref "J2") (pin "14") (pinfunction "14_14") (pintype "passive"))
      (node (ref "U1") (pin "32") (pinfunction "GPIO36/SPIIO7/FSPICLK/SUBSPICLK_32") (pintype "passive"))
    )
    (net (code "47") (name "/GPIO37") (class "Default")
      (node (ref "J2") (pin "13") (pinfunction "13_13") (pintype "passive"))
      (node (ref "U1") (pin "33") (pinfunction "GPIO37/SPIDQS/FSPIQ/SUBSPIQ_33") (pintype "passive"))
    )
    (net (code "48") (name "/GPIO38") (class "Default")
      (node (ref "J2") (pin "12") (pinfunction "12_12") (pintype "passive"))
      (node (ref "U1") (pin "34") (pinfunction "GPIO38/FSPIWP/SUBSPIWP_34") (pintype "passive"))
    )
    (net (code "49") (name "/GPIO39") (class "Default")
      (node (ref "J2") (pin "11") (pinfunction "11_11") (pintype "passive"))
      (node (ref "U1") (pin "35") (pinfunction "MTCK/GPIO39/CLK_OUT3/SUBSPICS1_35") (pintype "passive"))
    )
    (net (code "50") (name "/GPIO40") (class "Default")
      (node (ref "J2") (pin "10") (pinfunction "10_10") (pintype "passive"))
      (node (ref "U1") (pin "36") (pinfunction "MTDO/GPIO40/CLK_OUT2_36") (pintype "passive"))
    )
    (net (code "51") (name "/GPIO41") (class "Default")
      (node (ref "J2") (pin "9") (pinfunction "9_9") (pintype "passive"))
      (node (ref "U1") (pin "37") (pinfunction "MTDI/GPIO41/CLK_OUT1_37") (pintype "passive"))
    )
    (net (code "52") (name "/GPIO42") (class "Default")
      (node (ref "J2") (pin "8") (pinfunction "8_8") (pintype "passive"))
      (node (ref "U1") (pin "38") (pinfunction "MTMS/GPIO42_38") (pintype "passive"))
    )
    (net (code "53") (name "/GPIO45") (class "Default")
      (node (ref "J2") (pin "5") (pinfunction "5_5") (pintype "passive"))
      (node (ref "U1") (pin "41") (pinfunction "GPIO45_41") (pintype "passive"))
    )
    (net (code "54") (name "/GPIO46") (class "Default")
      (node (ref "J2") (pin "4") (pinfunction "4_4") (pintype "passive"))
      (node (ref "U1") (pin "44") (pinfunction "GPIO46_44") (pintype "passive"))
    )
    (net (code "55") (name "/GPIO47") (class "Default")
      (node (ref "J2") (pin "23") (pinfunction "23_23") (pintype "passive"))
      (node (ref "U1") (pin "27") (pinfunction "GPIO47/SPICLK_P_DIFF/SUBSPICLK_P_DIFF_27") (pintype "passive"))
    )
    (net (code "56") (name "/GPIO48") (class "Default")
      (node (ref "J2") (pin "22") (pinfunction "22_22") (pintype "passive"))
      (node (ref "U1") (pin "30") (pinfunction "GPIO48/SPICLK_N_DIFF/SUBSPICLK_N_DIFF_30") (pintype "passive"))
    )
    (net (code "57") (name "/RTS_FTDI") (class "Default")
      (node (ref "Q1") (pin "2") (pinfunction "E_2") (pintype "passive"))
      (node (ref "R17") (pin "2") (pinfunction "2_2") (pintype "passive"))
      (node (ref "U2") (pin "19") (pinfunction "~{RTS}_19") (pintype "passive"))
    )
    (net (code "58") (name "/RXD_FTDI") (class "Default")
      (node (ref "R19") (pin "2") (pinfunction "2_2") (pintype "passive"))
      (node (ref "U2") (pin "1") (pinfunction "RXD_1") (pintype "passive"))
    )
    (net (code "59") (name "/TXD_FTDI") (class "Default")
      (node (ref "R20") (pin "2") (pinfunction "2_2") (pintype "passive"))
      (node (ref "U2") (pin "17") (pinfunction "TXD_17") (pintype "passive"))
    )
    (net (code "60") (name "/U0RXD") (class "Default")
      (node (ref "J2") (pin "6") (pinfunction "6_6") (pintype "passive"))
      (node (ref "R20") (pin "1") (pinfunction "1_1") (pintype "passive"))
      (node (ref "U1") (pin "40") (pinfunction "U0RXD/GPIO44/CLK_OUT2_40") (pintype "passive"))
    )
    (net (code "61") (name "/U0TXD") (class "Default")
      (node (ref "J2") (pin "7") (pinfunction "7_7") (pintype "passive"))
      (node (ref "R19") (pin "1") (pinfunction "1_1") (pintype "passive"))
      (node (ref "U1") (pin "39") (pinfunction "U0TXD/GPIO43/CLK_OUT1_39") (pintype "passive"))
    )
    (net (code "62") (name "/VBUS_SENSE") (class "Default")
      (node (ref "R10") (pin "1") (pinfunction "1_1") (pintype "passive"))
      (node (ref "R13") (pin "2") (pinfunction "2_2") (pintype "passive"))
      (node (ref "U2") (pin "16") (pinfunction "CBUS3_16") (pintype "passive"))
    )
    (net (code "63") (name "GND") (class "Default")
      (node (ref "C1") (pin "1") (pinfunction "1_1") (pintype "passive"))
      (node (ref "C10") (pin "1") (pinfunction "1_1") (pintype "passive"))
      (node (ref "C11") (pin "1") (pinfunction "1_1") (pintype "passive"))
      (node (ref "C12") (pin "1") (pinfunction "1_1") (pintype "passive"))
      (node (ref "C13") (pin "1") (pinfunction "1_1") (pintype "passive"))
      (node (ref "C14") (pin "1") (pinfunction "1_1") (pintype "passive"))
      (node (ref "C15") (pin "1") (pinfunction "1_1") (pintype "passive"))
      (node (ref "C16") (pin "1") (pinfunction "1_1") (pintype "passive"))
      (node (ref "C17") (pin "1") (pinfunction "1_1") (pintype "passive"))
      (node (ref "C2") (pin "1") (pinfunction "1_1") (pintype "passive"))
      (node (ref "C3") (pin "1") (pinfunction "1_1") (pintype "passive"))
      (node (ref "C4") (pin "1") (pinfunction "1_1") (pintype "passive"))
      (node (ref "C5") (pin "1") (pinfunction "1_1") (pintype "passive"))
      (node (ref "C6") (pin "1") (pinfunction "1_1") (pintype "passive"))
      (node (ref "C7") (pin "1") (pinfunction "1_1") (pintype "passive"))
      (node (ref "C8") (pin "1") (pinfunction "1_1") (pintype "passive"))
      (node (ref "C9") (pin "1") (pinfunction "1_1") (pintype "passive"))
      (node (ref "D1") (pin "1") (pinfunction "1_1") (pintype "passive"))
      (node (ref "D3") (pin "1") (pinfunction "1_1") (pintype "passive"))
      (node (ref "D4") (pin "1") (pinfunction "1_1") (pintype "passive"))
      (node (ref "D5") (pin "1") (pinfunction "1_1") (pintype "passive"))
      (node (ref "D6") (pin "1") (pinfunction "1_1") (pintype "passive"))
      (node (ref "D7") (pin "1") (pinfunction "1_1") (pintype "passive"))
      (node (ref "D8") (pin "1") (pinfunction "1_1") (pintype "passive"))
      (node (ref "J1") (pin "1") (pinfunction "1_1") (pintype "passive"))
      (node (ref "J1") (pin "23") (pinfunction "23_23") (pintype "passive"))
      (node (ref "J2") (pin "2") (pinfunction "2_2") (pintype "passive"))
      (node (ref "J2") (pin "24") (pinfunction "24_24") (pintype "passive"))
      (node (ref "J3") (pin "A1B12") (pinfunction "GND_A1B12_A1B12") (pintype "passive"))
      (node (ref "J3") (pin "B1A12") (pinfunction "GND_B1A12_B1A12") (pintype "passive"))
      (node (ref "J3") (pin "S1") (pinfunction "SHIELD_S1_S1") (pintype "passive"))
      (node (ref "J3") (pin "S2") (pinfunction "SHIELD_S2_S2") (pintype "passive"))
      (node (ref "J3") (pin "S3") (pinfunction "SHIELD_S3_S3") (pintype "passive"))
      (node (ref "J3") (pin "S4") (pinfunction "SHIELD_S4_S4") (pintype "passive"))
      (node (ref "J4") (pin "A1B12") (pinfunction "GND_A1B12_A1B12") (pintype "passive"))
      (node (ref "J4") (pin "B1A12") (pinfunction "GND_B1A12_B1A12") (pintype "passive"))
      (node (ref "J4") (pin "S1") (pinfunction "SHIELD_S1_S1") (pintype "passive"))
      (node (ref "J4") (pin "S2") (pinfunction "SHIELD_S2_S2") (pintype "passive"))
      (node (ref "J4") (pin "S3") (pinfunction "SHIELD_S3_S3") (pintype "passive"))
      (node (ref "J4") (pin "S4") (pinfunction "SHIELD_S4_S4") (pintype "passive"))
      (node (ref "R11") (pin "1") (pinfunction "1_1") (pintype "passive"))
      (node (ref "R12") (pin "1") (pinfunction "1_1") (pintype "passive"))
      (node (ref "R13") (pin "1") (pinfunction "1_1") (pintype "passive"))
      (node (ref "R15") (pin "1") (pinfunction "1_1") (pintype "passive"))
      (node (ref "R16") (pin "1") (pinfunction "1_1") (pintype "passive"))
      (node (ref "R9") (pin "2") (pinfunction "2_2") (pintype "passive"))
      (node (ref "SW1") (pin "3") (pinfunction "3_3") (pintype "passive"))
      (node (ref "SW1") (pin "4") (pinfunction "4_4") (pintype "passive"))
      (node (ref "SW2") (pin "3") (pinfunction "3_3") (pintype "passive"))
      (node (ref "SW2") (pin "4") (pinfunction "4_4") (pintype "passive"))
      (node (ref "U1") (pin "1") (pinfunction "GND_01_1") (pintype "passive"))
      (node (ref "U1") (pin "2") (pinfunction "GND_02_2") (pintype "passive"))
      (node (ref "U1") (pin "42") (pinfunction "GND_42") (pintype "passive"))
      (node (ref "U1") (pin "43") (pinfunction "GND_43") (pintype "passive"))
      (node (ref "U1") (pin "46") (pinfunction "GND_46_46") (pintype "passive"))
      (node (ref "U1") (pin "47") (pinfunction "GND_47_47") (pintype "passive"))
      (node (ref "U1") (pin "48") (pinfunction "GND_48_48") (pintype "passive"))
      (node (ref "U1") (pin "49") (pinfunction "GND_49_49") (pintype "passive"))
      (node (ref "U1") (pin "50") (pinfunction "GND_50_50") (pintype "passive"))
      (node (ref "U1") (pin "51") (pinfunction "GND_51_51") (pintype "passive"))
      (node (ref "U1") (pin "52") (pinfunction "GND_52_52") (pintype "passive"))
      (node (ref "U1") (pin "53") (pinfunction "GND_53_53") (pintype "passive"))
      (node (ref "U1") (pin "54") (pinfunction "GND_54_54") (pintype "passive"))
      (node (ref "U1") (pin "55") (pinfunction "GND_55_55") (pintype "passive"))
      (node (ref "U1") (pin "56") (pinfunction "GND_56_56") (pintype "passive"))
      (node (ref "U1") (pin "57") (pinfunction "GND_57_57") (pintype "passive"))
      (node (ref "U1") (pin "58") (pinfunction "GND_58_58") (pintype "passive"))
      (node (ref "U1") (pin "59") (pinfunction "GND_59_59") (pintype "passive"))
      (node (ref "U1") (pin "60") (pinfunction "GND_60_60") (pintype "passive"))
      (node (ref "U1") (pin "61") (pinfunction "GND_61_61") (pintype "passive"))
      (node (ref "U1") (pin "62") (pinfunction "GND_62_62") (pintype "passive"))
      (node (ref "U1") (pin "63") (pinfunction "GND_63_63") (pintype "passive"))
      (node (ref "U1") (pin "64") (pinfunction "GND_64_64") (pintype "passive"))
      (node (ref "U1") (pin "65") (pinfunction "GND_65_65") (pintype "passive"))
      (node (ref "U1") (pin "66") (pinfunction "GND_66_66") (pintype "passive"))
      (node (ref "U1") (pin "67") (pinfunction "GND_67_67") (pintype "passive"))
      (node (ref "U1") (pin "68") (pinfunction "GND_68_68") (pintype "passive"))
      (node (ref "U1") (pin "69") (pinfunction "GND_69_69") (pintype "passive"))
      (node (ref "U1") (pin "70") (pinfunction "GND_70_70") (pintype "passive"))
      (node (ref "U1") (pin "71") (pinfunction "GND_71_71") (pintype "passive"))
      (node (ref "U1") (pin "72") (pinfunction "GND_72_72") (pintype "passive"))
      (node (ref "U1") (pin "73") (pinfunction "GND_73_73") (pintype "passive"))
      (node (ref "U2") (pin "13") (pinfunction "GND_13") (pintype "passive"))
      (node (ref "U2") (pin "21") (pinfunction "GND_21") (pintype "passive"))
      (node (ref "U2") (pin "3") (pinfunction "GND_3") (pintype "passive"))
      (node (ref "U3") (pin "2") (pinfunction "GND_2") (pintype "power_in"))
      (node (ref "U3") (pin "4") (pinfunction "GND_4") (pintype "power_in"))
    )
    (net (code "64") (name "Net-(D1-Pad2)") (class "Default")
      (node (ref "D1") (pin "2") (pinfunction "2_2") (pintype "passive"))
      (node (ref "R3") (pin "1") (pinfunction "1_1") (pintype "passive"))
    )
    (net (code "65") (name "Net-(D2-Pad2)") (class "Default")
      (node (ref "D2") (pin "2") (pinfunction "2_2") (pintype "passive"))
      (node (ref "R4") (pin "1") (pinfunction "1_1") (pintype "passive"))
    )
    (net (code "66") (name "Net-(J3-CC1)") (class "Default")
      (node (ref "J3") (pin "A5") (pinfunction "CC1_A5") (pintype "passive"))
      (node (ref "R12") (pin "2") (pinfunction "2_2") (pintype "passive"))
    )
    (net (code "67") (name "Net-(J3-CC2)") (class "Default")
      (node (ref "J3") (pin "B5") (pinfunction "CC2_B5") (pintype "passive"))
      (node (ref "R11") (pin "2") (pinfunction "2_2") (pintype "passive"))
    )
    (net (code "68") (name "Net-(J4-CC1)") (class "Default")
      (node (ref "J4") (pin "A5") (pinfunction "CC1_A5") (pintype "passive"))
      (node (ref "R16") (pin "2") (pinfunction "2_2") (pintype "passive"))
    )
    (net (code "69") (name "Net-(J4-CC2)") (class "Default")
      (node (ref "J4") (pin "B5") (pinfunction "CC2_B5") (pintype "passive"))
      (node (ref "R15") (pin "2") (pinfunction "2_2") (pintype "passive"))
    )
    (net (code "70") (name "Net-(Q1-B)") (class "Default")
      (node (ref "Q1") (pin "1") (pinfunction "B_1") (pintype "passive"))
      (node (ref "R14") (pin "1") (pinfunction "1_1") (pintype "passive"))
    )
    (net (code "71") (name "Net-(Q2-B)") (class "Default")
      (node (ref "Q2") (pin "1") (pinfunction "B_1") (pintype "passive"))
      (node (ref "R17") (pin "1") (pinfunction "1_1") (pintype "passive"))
    )
    (net (code "72") (name "Net-(U2-CBUS0)") (class "Default")
      (node (ref "R9") (pin "1") (pinfunction "1_1") (pintype "passive"))
      (node (ref "U2") (pin "15") (pinfunction "CBUS0_15") (pintype "passive"))
    )
    (net (code "73") (name "Net-(U2-~{RESET})") (class "Default")
      (node (ref "C8") (pin "2") (pinfunction "2_2") (pintype "passive"))
      (node (ref "R8") (pin "2") (pinfunction "2_2") (pintype "passive"))
      (node (ref "U2") (pin "11") (pinfunction "~{RESET}_11") (pintype "passive"))
    )
    (net (code "74") (name "unconnected-(J1-Pad24)") (class "Default")
      (node (ref "J1") (pin "24") (pinfunction "24_24") (pintype "passive+no_connect"))
    )
    (net (code "75") (name "unconnected-(J3-SBU1-PadA8)") (class "Default")
      (node (ref "J3") (pin "A8") (pinfunction "SBU1_A8") (pintype "passive+no_connect"))
    )
    (net (code "76") (name "unconnected-(J3-SBU2-PadB8)") (class "Default")
      (node (ref "J3") (pin "B8") (pinfunction "SBU2_B8") (pintype "passive+no_connect"))
    )
    (net (code "77") (name "unconnected-(J4-SBU1-PadA8)") (class "Default")
      (node (ref "J4") (pin "A8") (pinfunction "SBU1_A8") (pintype "passive+no_connect"))
    )
    (net (code "78") (name "unconnected-(J4-SBU2-PadB8)") (class "Default")
      (node (ref "J4") (pin "B8") (pinfunction "SBU2_B8") (pintype "passive+no_connect"))
    )
    (net (code "79") (name "unconnected-(U2-CBUS1-Pad14)") (class "Default")
      (node (ref "U2") (pin "14") (pinfunction "CBUS1_14") (pintype "passive+no_connect"))
    )
    (net (code "80") (name "unconnected-(U2-CBUS2-Pad7)") (class "Default")
      (node (ref "U2") (pin "7") (pinfunction "CBUS2_7") (pintype "passive+no_connect"))
    )
    (net (code "81") (name "unconnected-(U2-~{CTS}-Pad6)") (class "Default")
      (node (ref "U2") (pin "6") (pinfunction "~{CTS}_6") (pintype "passive+no_connect"))
    )
    (net (code "82") (name "unconnected-(U2-~{DCD}-Pad5)") (class "Default")
      (node (ref "U2") (pin "5") (pinfunction "~{DCD}_5") (pintype "passive+no_connect"))
    )
    (net (code "83") (name "unconnected-(U2-~{DSR}-Pad4)") (class "Default")
      (node (ref "U2") (pin "4") (pinfunction "~{DSR}_4") (pintype "passive+no_connect"))
    )
    (net (code "84") (name "unconnected-(U2-~{RI}-Pad2)") (class "Default")
      (node (ref "U2") (pin "2") (pinfunction "~{RI}_2") (pintype "passive+no_connect"))
    )
  )
)
